# SH3_-_17V_BUCK_CONVERTER.net
KiCad netlist of a schematic drawn in Altium Designer
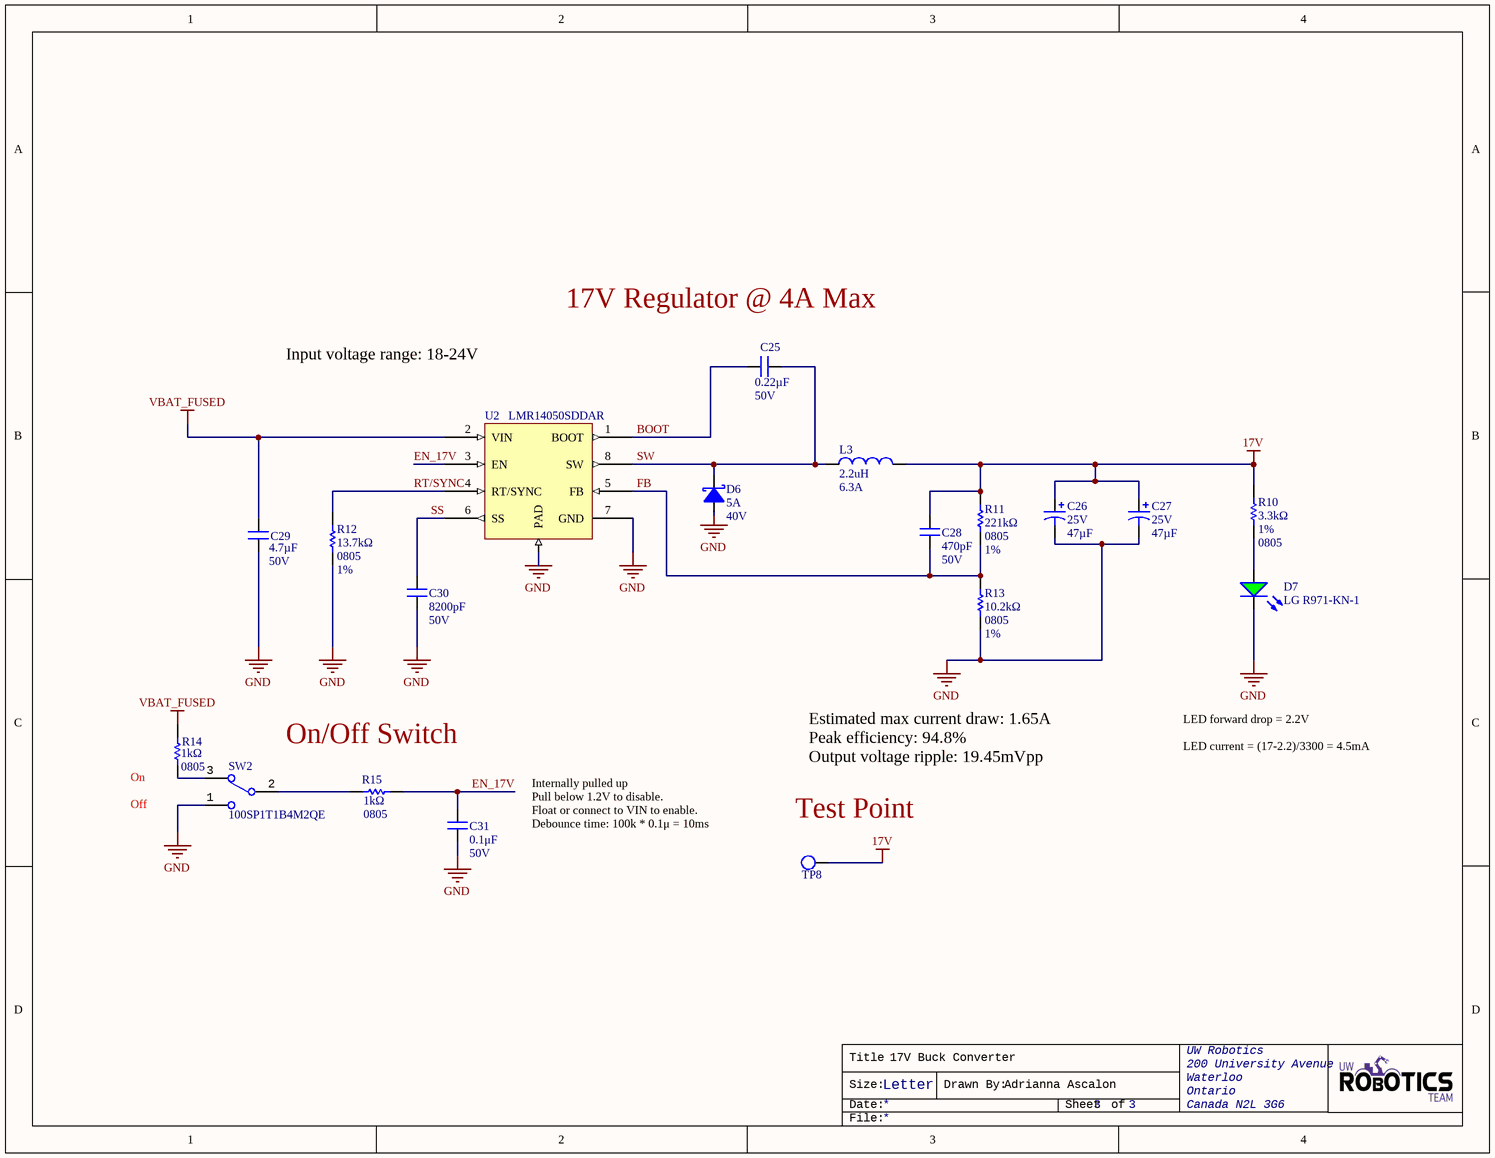
[diagram p0: SH3 - 17V BUCK CONVERTER.SchDoc]

(export (version "E")
  (design (tool "Eeschema 10.0.6"))
  (components
    (comp (ref "C25")
      (value "GRM21BR71H224MA01L")
      (footprint "CAP 0805_2012")
      (description "CAP CER 0.22UF 50V X7R 0805")
      (fields
        (field (name "TOLERANCE") "20%")
        (field (name "VOLTAGE RATING") "50V")
        (field (name "CAPACITANCE") "0.22µF")
      )
      (libsource (lib "UWRT_Schematic_Library_2020") (part "GRM21BR71H224MA01L"))
    )
    (comp (ref "C26")
      (value "47μF")
      (footprint "25SVPF47M")
      (description "CAP ALUM POLY 47UF 20% 25V SMD")
      (fields
        (field (name "TOLERANCE") "20%")
        (field (name "VOLTAGE") "25V")
        (field (name "CAPACITANCE") "47µF")
      )
      (libsource (lib "UWRT_Schematic_Library_2020") (part "25SVPF47M"))
    )
    (comp (ref "C27")
      (value "47μF")
      (footprint "25SVPF47M")
      (description "CAP ALUM POLY 47UF 20% 25V SMD")
      (fields
        (field (name "TOLERANCE") "20%")
        (field (name "VOLTAGE") "25V")
        (field (name "CAPACITANCE") "47µF")
      )
      (libsource (lib "UWRT_Schematic_Library_2020") (part "25SVPF47M"))
    )
    (comp (ref "C28")
      (value "470pF")
      (footprint "CAP 0805_2012")
      (description "CAP CER 470PF 50V X7R 0805")
      (fields (field (name "VOLTAGE RATING") "50V") (field (name "TOLERANCE") "5%"))
      (libsource (lib "UWRT_Schematic_Library_2020") (part "CAP_470pF_50V_0805"))
    )
    (comp (ref "C29")
      (value "GRM31CR71H475KA12L")
      (footprint "CAPC1206(3216)")
      (description "CAP CER 4.7UF 50V X7R 1206")
      (fields
        (field (name "TOLERANCE") "10%")
        (field (name "VOLTAGE") "50V")
        (field (name "VOLTAGE RATING") "50V")
        (field (name "CAPACITANCE") "4.7µF")
      )
      (libsource (lib "UWRT_Schematic_Library_2020") (part "GRM31CR71H475KA12L"))
    )
    (comp (ref "C30")
      (value "8200pF")
      (footprint "CAP 0805_2012")
      (description "CAP CER 8200PF 50V X7R 0805")
      (fields (field (name "TOLERANCE") "10%") (field (name "VOLTAGE RATING") "50V"))
      (libsource (lib "UWRT_Schematic_Library_2020") (part "CAP_8200pF_50V_0805"))
    )
    (comp (ref "C31")
      (value "0.1μF")
      (footprint "CAPC2012X140N")
      (description "CAP CER 0.1UF 50V X7R 0805")
      (fields (field (name "VOLTAGE RATING") "50V") (field (name "TOLERANCE") "10%"))
      (libsource (lib "UWRT_Schematic_Library_2020") (part "CAP_0.1uF_50V_0805"))
    )
    (comp (ref "D6")
      (value "B540C-13-F")
      (footprint "DO214AB SMC")
      (description "DIODE SCHOTTKY 40V 5A SMC")
      (fields (field (name "FORWARD CURRENT") "5A") (field (name "VOLTAGE") "40V"))
      (libsource (lib "UWRT_Schematic_Library_2020") (part "B540C-13-F"))
    )
    (comp (ref "D7")
      (value "LG R971-KN-1")
      (footprint "LED_0805_LINE")
      (description "LED GREEN DIFFUSED 0805 SMD")
      (libsource (lib "UWRT_Schematic_Library_2020") (part "DIO_LED_G"))
    )
    (comp (ref "L3")
      (value "SRN8040-2R2Y")
      (footprint "IND_BOURNS_SRN80")
      (description "FIXED IND 2.2UH 6.3A 13 MOHM SMD")
      (fields
        (field (name "TOLERANCE") "30%")
        (field (name "INDUCTANCE") "2.2uH")
        (field (name "MAX DC CURRENT") "6.3A")
      )
      (libsource (lib "UWRT_Schematic_Library_2020") (part "SRN8040-2R2Y"))
    )
    (comp (ref "R10")
      (value "3.3kΩ")
      (footprint "RESC2012X60N")
      (description "RES SMD 3.3K OHM 1% 1/8W 0805")
      (fields (field (name "TOLERANCE") "1%") (field (name "CASE CODE (IMPERIAL)") "0805"))
      (libsource (lib "UWRT_Schematic_Library_2020") (part "RES_3.3kΩ_0805"))
    )
    (comp (ref "R11")
      (value "221kΩ")
      (footprint "RESC2012X60N")
      (description "RES SMD 221K OHM 1% 1/8W 0805")
      (fields (field (name "CASE CODE (IMPERIAL)") "0805") (field (name "TOLERANCE") "1%"))
      (libsource (lib "UWRT_Schematic_Library_2020") (part "RES_221kΩ_0805"))
    )
    (comp (ref "R12")
      (value "13.7kΩ")
      (footprint "RESC2012X60N")
      (description "RES SMD 13.7K OHM 1% 1/8W 0805")
      (fields (field (name "CASE CODE (IMPERIAL)") "0805") (field (name "TOLERANCE") "1%"))
      (libsource (lib "UWRT_Schematic_Library_2020") (part "RES_13.7kΩ_0805"))
    )
    (comp (ref "R13")
      (value "10.2kΩ")
      (footprint "RESC2012X60N")
      (description "RES SMD 10.2K OHM 1% 1/8W 0805")
      (fields (field (name "CASE CODE (IMPERIAL)") "0805") (field (name "TOLERANCE") "1%"))
      (libsource (lib "UWRT_Schematic_Library_2020") (part "RES_10.2kΩ_0805"))
    )
    (comp (ref "R14")
      (value "1kΩ")
      (footprint "RESC2012X60N")
      (description "RES SMD 1K OHM 1% 1/8W 0805")
      (fields (field (name "TOLERANCE") "1%") (field (name "CASE CODE (IMPERIAL)") "0805"))
      (libsource (lib "UWRT_Schematic_Library_2020") (part "RES_1kΩ_0805"))
    )
    (comp (ref "R15")
      (value "1kΩ")
      (footprint "RESC2012X60N")
      (description "RES SMD 100K OHM 0.5% 1/8W 0805")
      (fields (field (name "TOLERANCE") "0.5%") (field (name "CASE CODE (IMPERIAL)") "0805"))
      (libsource (lib "UWRT_Schematic_Library_2020") (part "RES_100kΩ_0805"))
    )
    (comp (ref "SW2")
      (value "100SP1T1B4M2QE")
      (footprint "100SP1T1B4M2QE")
      (description "SWITCH TOGGLE SPDT 5A 120V")
      (libsource (lib "UWRT_Schematic_Library_2020") (part "SW_SPDT"))
    )
    (comp (ref "TP8")
      (value "TESTPOINT_LOOP")
      (footprint "TESTPOINT_LOOP")
      (description "PC TEST POINT MINIATURE WHITE")
      (libsource (lib "UWRT_Schematic_Library_2020") (part "TESTPOINT_LOOP"))
    )
    (comp (ref "U2")
      (value "LMR14050SDDAR")
      (footprint "8-PowerSOIC")
      (description "IC REG BUCK ADJUSTABLE 5A 8SOPWR")
      (libsource (lib "UWRT_Schematic_Library_2020") (part "LMR14050SDDAR"))
    )
  )
  (nets
    (net (code "1") (name "/BOOT") (class "Default")
      (node (ref "C25") (pin "2") (pinfunction "2_2") (pintype "passive"))
      (node (ref "U2") (pin "1") (pinfunction "BOOT_1") (pintype "output"))
    )
    (net (code "2") (name "/EN_17V") (class "Default")
      (node (ref "C31") (pin "2") (pinfunction "2_2") (pintype "passive"))
      (node (ref "R15") (pin "2") (pinfunction "2_2") (pintype "passive"))
      (node (ref "U2") (pin "3") (pinfunction "EN_3") (pintype "input"))
    )
    (net (code "3") (name "/FB") (class "Default")
      (node (ref "C28") (pin "1") (pinfunction "1_1") (pintype "passive"))
      (node (ref "R11") (pin "1") (pinfunction "1_1") (pintype "passive"))
      (node (ref "R13") (pin "2") (pinfunction "2_2") (pintype "passive"))
      (node (ref "U2") (pin "5") (pinfunction "FB_5") (pintype "input"))
    )
    (net (code "4") (name "/RT{slash}SYNC") (class "Default")
      (node (ref "R12") (pin "2") (pinfunction "2_2") (pintype "passive"))
      (node (ref "U2") (pin "4") (pinfunction "RT/SYNC_4") (pintype "input"))
    )
    (net (code "5") (name "/SS") (class "Default")
      (node (ref "C30") (pin "2") (pinfunction "2_2") (pintype "passive"))
      (node (ref "U2") (pin "6") (pinfunction "SS_6") (pintype "output"))
    )
    (net (code "6") (name "/SW") (class "Default")
      (node (ref "C25") (pin "1") (pinfunction "1_1") (pintype "passive"))
      (node (ref "D6") (pin "2") (pinfunction "Cathode_2") (pintype "passive"))
      (node (ref "L3") (pin "1") (pinfunction "1_1") (pintype "passive"))
      (node (ref "U2") (pin "8") (pinfunction "SW_8") (pintype "output"))
    )
    (net (code "7") (name "17V") (class "Default")
      (node (ref "C26") (pin "1") (pinfunction "1_1") (pintype "passive"))
      (node (ref "C27") (pin "1") (pinfunction "1_1") (pintype "passive"))
      (node (ref "C28") (pin "2") (pinfunction "2_2") (pintype "passive"))
      (node (ref "L3") (pin "2") (pinfunction "2_2") (pintype "passive"))
      (node (ref "R10") (pin "2") (pinfunction "2_2") (pintype "passive"))
      (node (ref "R11") (pin "2") (pinfunction "2_2") (pintype "passive"))
      (node (ref "TP8") (pin "1") (pintype "passive"))
    )
    (net (code "8") (name "GND") (class "Default")
      (node (ref "C26") (pin "2") (pinfunction "2_2") (pintype "passive"))
      (node (ref "C27") (pin "2") (pinfunction "2_2") (pintype "passive"))
      (node (ref "C29") (pin "2") (pinfunction "2_2") (pintype "passive"))
      (node (ref "C30") (pin "1") (pinfunction "1_1") (pintype "passive"))
      (node (ref "C31") (pin "1") (pinfunction "1_1") (pintype "passive"))
      (node (ref "D6") (pin "1") (pinfunction "Anode_1") (pintype "passive"))
      (node (ref "D7") (pin "2") (pinfunction "K_2") (pintype "passive"))
      (node (ref "R12") (pin "1") (pinfunction "1_1") (pintype "passive"))
      (node (ref "R13") (pin "1") (pinfunction "1_1") (pintype "passive"))
      (node (ref "SW2") (pin "1") (pinfunction "1_1") (pintype "passive"))
      (node (ref "U2") (pin "7") (pinfunction "GND_7") (pintype "power_in"))
      (node (ref "U2") (pin "9") (pinfunction "PAD_9") (pintype "input"))
    )
    (net (code "9") (name "Net-(D7-A)") (class "Default")
      (node (ref "D7") (pin "1") (pinfunction "A_1") (pintype "passive"))
      (node (ref "R10") (pin "1") (pinfunction "1_1") (pintype "passive"))
    )
    (net (code "10") (name "Net-(R14-Pad1)") (class "Default")
      (node (ref "R14") (pin "1") (pinfunction "1_1") (pintype "passive"))
      (node (ref "SW2") (pin "3") (pinfunction "3_3") (pintype "passive"))
    )
    (net (code "11") (name "Net-(R15-Pad1)") (class "Default")
      (node (ref "R15") (pin "1") (pinfunction "1_1") (pintype "passive"))
      (node (ref "SW2") (pin "2") (pinfunction "2_2") (pintype "passive"))
    )
    (net (code "12") (name "VBAT_FUSED") (class "Default")
      (node (ref "C29") (pin "1") (pinfunction "1_1") (pintype "passive"))
      (node (ref "R14") (pin "2") (pinfunction "2_2") (pintype "passive"))
      (node (ref "U2") (pin "2") (pinfunction "VIN_2") (pintype "input"))
    )
  )
)
